# PowerSystem.net
KiCad netlist of a schematic drawn in Altium Designer
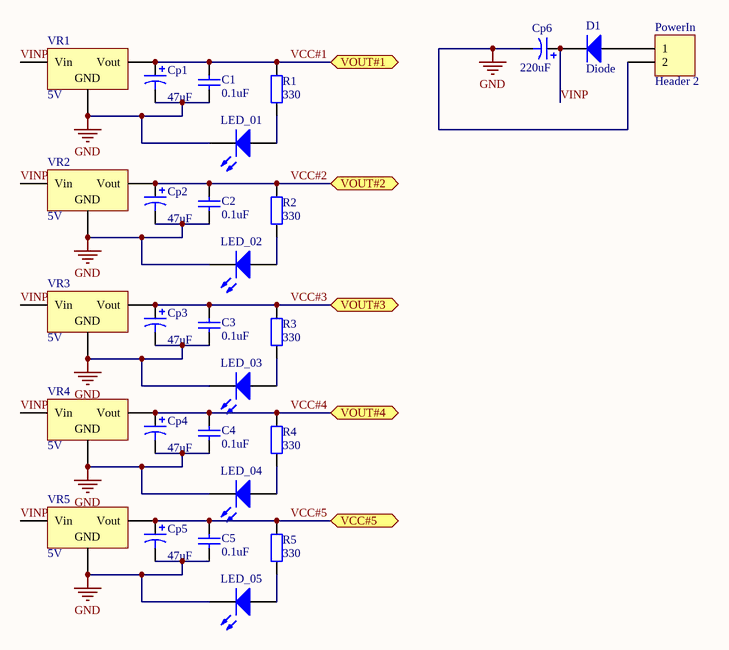
[diagram p0: PowerSystem.SchDoc]

(export (version "E")
  (design (tool "Eeschema 10.0.6"))
  (components
    (comp (ref "C1")
      (value "0.1uF")
      (footprint "6-0805_N")
      (description "Capacitor (Semiconductor SIM Model)")
      (fields (field (name "Comment") "Cap Semi") (field (name "PUBLISHER") "Altium Limited"))
      (libsource (lib "Miscellaneous Devices") (part "Cap Semi"))
    )
    (comp (ref "C2")
      (value "0.1uF")
      (footprint "6-0805_N")
      (description "Capacitor (Semiconductor SIM Model)")
      (fields (field (name "Comment") "Cap Semi") (field (name "PUBLISHER") "Altium Limited"))
      (libsource (lib "Miscellaneous Devices") (part "Cap Semi"))
    )
    (comp (ref "C3")
      (value "0.1uF")
      (footprint "6-0805_N")
      (description "Capacitor (Semiconductor SIM Model)")
      (fields (field (name "Comment") "Cap Semi") (field (name "PUBLISHER") "Altium Limited"))
      (libsource (lib "Miscellaneous Devices") (part "Cap Semi"))
    )
    (comp (ref "C4")
      (value "0.1uF")
      (footprint "6-0805_N")
      (description "Capacitor (Semiconductor SIM Model)")
      (fields (field (name "Comment") "Cap Semi") (field (name "PUBLISHER") "Altium Limited"))
      (libsource (lib "Miscellaneous Devices") (part "Cap Semi"))
    )
    (comp (ref "C5")
      (value "0.1uF")
      (footprint "6-0805_N")
      (description "Capacitor (Semiconductor SIM Model)")
      (fields (field (name "Comment") "Cap Semi") (field (name "PUBLISHER") "Altium Limited"))
      (libsource (lib "Miscellaneous Devices") (part "Cap Semi"))
    )
    (comp (ref "Cp1")
      (value "47uF")
      (footprint "1CA470WR")
      (description "Polarized Capacitor (Surface Mount)")
      (fields (field (name "Comment") "Cap Pol3") (field (name "PUBLISHER") "Altium Limited"))
      (libsource (lib "Miscellaneous Devices") (part "Cap Pol3"))
    )
    (comp (ref "Cp2")
      (value "47uF")
      (footprint "1CA470WR")
      (description "Polarized Capacitor (Surface Mount)")
      (fields (field (name "Comment") "Cap Pol3") (field (name "PUBLISHER") "Altium Limited"))
      (libsource (lib "Miscellaneous Devices") (part "Cap Pol3"))
    )
    (comp (ref "Cp3")
      (value "47uF")
      (footprint "1CA470WR")
      (description "Polarized Capacitor (Surface Mount)")
      (fields (field (name "Comment") "Cap Pol3") (field (name "PUBLISHER") "Altium Limited"))
      (libsource (lib "Miscellaneous Devices") (part "Cap Pol3"))
    )
    (comp (ref "Cp4")
      (value "47uF")
      (footprint "1CA470WR")
      (description "Polarized Capacitor (Surface Mount)")
      (fields (field (name "Comment") "Cap Pol3") (field (name "PUBLISHER") "Altium Limited"))
      (libsource (lib "Miscellaneous Devices") (part "Cap Pol3"))
    )
    (comp (ref "Cp5")
      (value "47uF")
      (footprint "1CA470WR")
      (description "Polarized Capacitor (Surface Mount)")
      (fields (field (name "Comment") "Cap Pol3") (field (name "PUBLISHER") "Altium Limited"))
      (libsource (lib "Miscellaneous Devices") (part "Cap Pol3"))
    )
    (comp (ref "Cp6")
      (value "220uF")
      (footprint "1CA470WR")
      (description "Polarized Capacitor (Surface Mount)")
      (fields (field (name "Comment") "Cap Pol3") (field (name "PUBLISHER") "Altium Limited"))
      (libsource (lib "Miscellaneous Devices") (part "Cap Pol3"))
    )
    (comp (ref "D1")
      (value "Diode")
      (footprint "SMC")
      (description "Default Diode")
      (fields (field (name "PUBLISHER") "Altium Limited"))
      (libsource (lib "Miscellaneous Devices") (part "Diode"))
    )
    (comp (ref "LED_01")
      (value "LED2")
      (footprint "3.2X1.6X1.1")
      (description "Typical RED, GREEN, YELLOW, AMBER GaAs LED")
      (fields (field (name "PUBLISHER") "Altium Limited"))
      (libsource (lib "Miscellaneous Devices") (part "LED2"))
    )
    (comp (ref "LED_02")
      (value "LED2")
      (footprint "3.2X1.6X1.1")
      (description "Typical RED, GREEN, YELLOW, AMBER GaAs LED")
      (fields (field (name "PUBLISHER") "Altium Limited"))
      (libsource (lib "Miscellaneous Devices") (part "LED2"))
    )
    (comp (ref "LED_03")
      (value "LED2")
      (footprint "3.2X1.6X1.1")
      (description "Typical RED, GREEN, YELLOW, AMBER GaAs LED")
      (fields (field (name "PUBLISHER") "Altium Limited"))
      (libsource (lib "Miscellaneous Devices") (part "LED2"))
    )
    (comp (ref "LED_04")
      (value "LED2")
      (footprint "3.2X1.6X1.1")
      (description "Typical RED, GREEN, YELLOW, AMBER GaAs LED")
      (fields (field (name "PUBLISHER") "Altium Limited"))
      (libsource (lib "Miscellaneous Devices") (part "LED2"))
    )
    (comp (ref "LED_05")
      (value "LED2")
      (footprint "3.2X1.6X1.1")
      (description "Typical RED, GREEN, YELLOW, AMBER GaAs LED")
      (fields (field (name "PUBLISHER") "Altium Limited"))
      (libsource (lib "Miscellaneous Devices") (part "LED2"))
    )
    (comp (ref "PowerIn")
      (value "Header 2")
      (footprint "Power Terminals")
      (description "Header, 2-Pin")
      (fields (field (name "PUBLISHER") "Altium Limited"))
      (libsource (lib "Miscellaneous Connectors") (part "Header 2"))
    )
    (comp (ref "R1")
      (value "330")
      (footprint "J1-0603")
      (description "Resistor")
      (fields (field (name "Comment") "Res2") (field (name "PUBLISHER") "Altium Limited"))
      (libsource (lib "Miscellaneous Devices") (part "Res2"))
    )
    (comp (ref "R2")
      (value "330")
      (footprint "J1-0603")
      (description "Resistor")
      (fields (field (name "Comment") "Res2") (field (name "PUBLISHER") "Altium Limited"))
      (libsource (lib "Miscellaneous Devices") (part "Res2"))
    )
    (comp (ref "R3")
      (value "330")
      (footprint "J1-0603")
      (description "Resistor")
      (fields (field (name "Comment") "Res2") (field (name "PUBLISHER") "Altium Limited"))
      (libsource (lib "Miscellaneous Devices") (part "Res2"))
    )
    (comp (ref "R4")
      (value "330")
      (footprint "J1-0603")
      (description "Resistor")
      (fields (field (name "Comment") "Res2") (field (name "PUBLISHER") "Altium Limited"))
      (libsource (lib "Miscellaneous Devices") (part "Res2"))
    )
    (comp (ref "R5")
      (value "330")
      (footprint "J1-0603")
      (description "Resistor")
      (fields (field (name "Comment") "Res2") (field (name "PUBLISHER") "Altium Limited"))
      (libsource (lib "Miscellaneous Devices") (part "Res2"))
    )
    (comp (ref "VR1")
      (value "5V")
      (footprint "SOT223_N")
      (description "Voltage Regulator")
      (fields (field (name "PUBLISHER") "Altium Limited"))
      (libsource (lib "Miscellaneous Devices") (part "Volt Reg"))
    )
    (comp (ref "VR2")
      (value "5V")
      (footprint "SOT223_N")
      (description "Voltage Regulator")
      (fields (field (name "PUBLISHER") "Altium Limited"))
      (libsource (lib "Miscellaneous Devices") (part "Volt Reg"))
    )
    (comp (ref "VR3")
      (value "5V")
      (footprint "SOT223_N")
      (description "Voltage Regulator")
      (fields (field (name "PUBLISHER") "Altium Limited"))
      (libsource (lib "Miscellaneous Devices") (part "Volt Reg"))
    )
    (comp (ref "VR4")
      (value "5V")
      (footprint "SOT223_N")
      (description "Voltage Regulator")
      (fields (field (name "PUBLISHER") "Altium Limited"))
      (libsource (lib "Miscellaneous Devices") (part "Volt Reg"))
    )
    (comp (ref "VR5")
      (value "5V")
      (footprint "SOT223_N")
      (description "Voltage Regulator")
      (fields (field (name "PUBLISHER") "Altium Limited"))
      (libsource (lib "Miscellaneous Devices") (part "Volt Reg"))
    )
  )
  (nets
    (net (code "1") (name "/VCC#1") (class "Default")
      (node (ref "C1") (pin "2") (pinfunction "2_2") (pintype "passive"))
      (node (ref "Cp1") (pin "1") (pinfunction "1_1") (pintype "passive"))
      (node (ref "R1") (pin "2") (pinfunction "2_2") (pintype "passive"))
      (node (ref "VR1") (pin "3") (pinfunction "Vout_3") (pintype "passive"))
    )
    (net (code "2") (name "/VCC#2") (class "Default")
      (node (ref "C2") (pin "2") (pinfunction "2_2") (pintype "passive"))
      (node (ref "Cp2") (pin "1") (pinfunction "1_1") (pintype "passive"))
      (node (ref "R2") (pin "2") (pinfunction "2_2") (pintype "passive"))
      (node (ref "VR2") (pin "3") (pinfunction "Vout_3") (pintype "passive"))
    )
    (net (code "3") (name "/VCC#3") (class "Default")
      (node (ref "C3") (pin "2") (pinfunction "2_2") (pintype "passive"))
      (node (ref "Cp3") (pin "1") (pinfunction "1_1") (pintype "passive"))
      (node (ref "R3") (pin "2") (pinfunction "2_2") (pintype "passive"))
      (node (ref "VR3") (pin "3") (pinfunction "Vout_3") (pintype "passive"))
    )
    (net (code "4") (name "/VCC#4") (class "Default")
      (node (ref "C4") (pin "2") (pinfunction "2_2") (pintype "passive"))
      (node (ref "Cp4") (pin "1") (pinfunction "1_1") (pintype "passive"))
      (node (ref "R4") (pin "2") (pinfunction "2_2") (pintype "passive"))
      (node (ref "VR4") (pin "3") (pinfunction "Vout_3") (pintype "passive"))
    )
    (net (code "5") (name "/VCC#5") (class "Default")
      (node (ref "C5") (pin "2") (pinfunction "2_2") (pintype "passive"))
      (node (ref "Cp5") (pin "1") (pinfunction "1_1") (pintype "passive"))
      (node (ref "R5") (pin "2") (pinfunction "2_2") (pintype "passive"))
      (node (ref "VR5") (pin "3") (pinfunction "Vout_3") (pintype "passive"))
    )
    (net (code "6") (name "/VINP") (class "Default")
      (node (ref "Cp6") (pin "1") (pinfunction "1_1") (pintype "passive"))
      (node (ref "D1") (pin "2") (pinfunction "K_2") (pintype "passive"))
      (node (ref "VR1") (pin "1") (pinfunction "Vin_1") (pintype "passive"))
      (node (ref "VR2") (pin "1") (pinfunction "Vin_1") (pintype "passive"))
      (node (ref "VR3") (pin "1") (pinfunction "Vin_1") (pintype "passive"))
      (node (ref "VR4") (pin "1") (pinfunction "Vin_1") (pintype "passive"))
      (node (ref "VR5") (pin "1") (pinfunction "Vin_1") (pintype "passive"))
    )
    (net (code "7") (name "GND") (class "Default")
      (node (ref "C1") (pin "1") (pinfunction "1_1") (pintype "passive"))
      (node (ref "C2") (pin "1") (pinfunction "1_1") (pintype "passive"))
      (node (ref "C3") (pin "1") (pinfunction "1_1") (pintype "passive"))
      (node (ref "C4") (pin "1") (pinfunction "1_1") (pintype "passive"))
      (node (ref "C5") (pin "1") (pinfunction "1_1") (pintype "passive"))
      (node (ref "Cp1") (pin "2") (pinfunction "2_2") (pintype "passive"))
      (node (ref "Cp2") (pin "2") (pinfunction "2_2") (pintype "passive"))
      (node (ref "Cp3") (pin "2") (pinfunction "2_2") (pintype "passive"))
      (node (ref "Cp4") (pin "2") (pinfunction "2_2") (pintype "passive"))
      (node (ref "Cp5") (pin "2") (pinfunction "2_2") (pintype "passive"))
      (node (ref "Cp6") (pin "2") (pinfunction "2_2") (pintype "passive"))
      (node (ref "LED_01") (pin "2") (pinfunction "K_2") (pintype "passive"))
      (node (ref "LED_02") (pin "2") (pinfunction "K_2") (pintype "passive"))
      (node (ref "LED_03") (pin "2") (pinfunction "K_2") (pintype "passive"))
      (node (ref "LED_04") (pin "2") (pinfunction "K_2") (pintype "passive"))
      (node (ref "LED_05") (pin "2") (pinfunction "K_2") (pintype "passive"))
      (node (ref "PowerIn") (pin "2") (pinfunction "2_2") (pintype "passive"))
      (node (ref "VR1") (pin "2") (pinfunction "GND_2") (pintype "passive"))
      (node (ref "VR2") (pin "2") (pinfunction "GND_2") (pintype "passive"))
      (node (ref "VR3") (pin "2") (pinfunction "GND_2") (pintype "passive"))
      (node (ref "VR4") (pin "2") (pinfunction "GND_2") (pintype "passive"))
      (node (ref "VR5") (pin "2") (pinfunction "GND_2") (pintype "passive"))
    )
    (net (code "8") (name "Net-(D1-A)") (class "Default")
      (node (ref "D1") (pin "1") (pinfunction "A_1") (pintype "passive"))
      (node (ref "PowerIn") (pin "1") (pinfunction "1_1") (pintype "passive"))
    )
    (net (code "9") (name "Net-(LED_01-A)") (class "Default")
      (node (ref "LED_01") (pin "1") (pinfunction "A_1") (pintype "passive"))
      (node (ref "R1") (pin "1") (pinfunction "1_1") (pintype "passive"))
    )
    (net (code "10") (name "Net-(LED_02-A)") (class "Default")
      (node (ref "LED_02") (pin "1") (pinfunction "A_1") (pintype "passive"))
      (node (ref "R2") (pin "1") (pinfunction "1_1") (pintype "passive"))
    )
    (net (code "11") (name "Net-(LED_03-A)") (class "Default")
      (node (ref "LED_03") (pin "1") (pinfunction "A_1") (pintype "passive"))
      (node (ref "R3") (pin "1") (pinfunction "1_1") (pintype "passive"))
    )
    (net (code "12") (name "Net-(LED_04-A)") (class "Default")
      (node (ref "LED_04") (pin "1") (pinfunction "A_1") (pintype "passive"))
      (node (ref "R4") (pin "1") (pinfunction "1_1") (pintype "passive"))
    )
    (net (code "13") (name "Net-(LED_05-A)") (class "Default")
      (node (ref "LED_05") (pin "1") (pinfunction "A_1") (pintype "passive"))
      (node (ref "R5") (pin "1") (pinfunction "1_1") (pintype "passive"))
    )
  )
)
